# LiPo_Battery_Charger_MCP73831.net
KiCad netlist of a schematic drawn in EAGLE
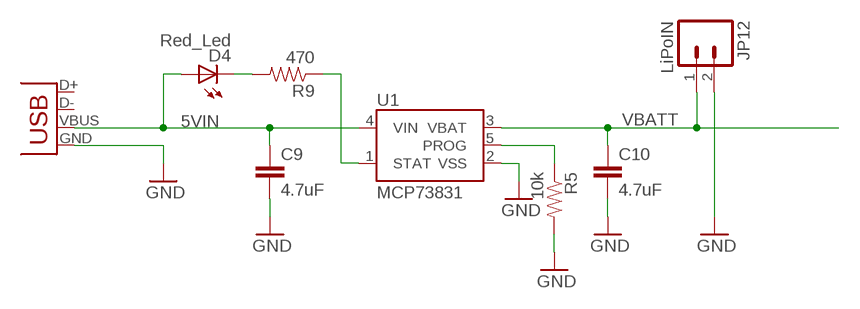
[diagram p0: schematic, sheet 1]

(export (version "E")
  (design (tool "Eeschema 10.0.6"))
  (components
    (comp (ref "C9")
      (value "4.7uF")
      (footprint "eagle-import:0402-CAP")
      (libsource (lib "eagle-import") (part "CAP0402-CAP"))
    )
    (comp (ref "C10")
      (value "4.7uF")
      (footprint "eagle-import:0402-CAP")
      (libsource (lib "eagle-import") (part "CAP0402-CAP"))
    )
    (comp (ref "D4")
      (value "Red_Led")
      (footprint "eagle-import:LED-0603")
      (libsource (lib "eagle-import") (part "LED0603"))
    )
    (comp (ref "JP12")
      (value "LiPoIN")
      (footprint "eagle-import:1X02")
      (libsource (lib "eagle-import") (part "M02PTH"))
    )
    (comp (ref "R5")
      (value "10k")
      (footprint "eagle-import:0402-RES")
      (libsource (lib "eagle-import") (part "RESISTOR0402-RES"))
    )
    (comp (ref "R9")
      (value "470")
      (footprint "eagle-import:0402-RES")
      (libsource (lib "eagle-import") (part "RESISTOR0402-RES"))
    )
    (comp (ref "U1")
      (value "MCP73831")
      (footprint "eagle-import:SOT23-5")
      (libsource (lib "eagle-import") (part "MCP73831"))
    )
    (comp (ref "X1")
      (value "USB-MICROB")
      (footprint "eagle-import:USB-MICROB")
      (libsource (lib "eagle-import") (part "USB-MICROB"))
    )
  )
  (nets
    (net (code "1") (name "/5VIN") (class "Default")
      (node (ref "C9") (pin "1") (pinfunction "1_1") (pintype "passive"))
      (node (ref "D4") (pin "A") (pinfunction "A_A") (pintype "passive"))
      (node (ref "U1") (pin "4") (pinfunction "VIN_4") (pintype "power_in"))
      (node (ref "X1") (pin "VBUS") (pinfunction "VBUS_VBUS") (pintype "bidirectional"))
    )
    (net (code "2") (name "/VBATT") (class "Default")
      (node (ref "C10") (pin "1") (pinfunction "1_1") (pintype "passive"))
      (node (ref "JP12") (pin "1") (pinfunction "1_1") (pintype "passive"))
      (node (ref "U1") (pin "3") (pinfunction "VBAT_3") (pintype "power_in"))
    )
    (net (code "3") (name "GND") (class "Default")
      (node (ref "C10") (pin "2") (pinfunction "2_2") (pintype "passive"))
      (node (ref "C9") (pin "2") (pinfunction "2_2") (pintype "passive"))
      (node (ref "JP12") (pin "2") (pinfunction "2_2") (pintype "passive"))
      (node (ref "R5") (pin "2") (pinfunction "2_2") (pintype "passive"))
      (node (ref "U1") (pin "2") (pinfunction "VSS_2") (pintype "power_in"))
      (node (ref "X1") (pin "GND") (pinfunction "GND_GND") (pintype "bidirectional"))
    )
    (net (code "4") (name "Net-(D4-PadC)") (class "Default")
      (node (ref "D4") (pin "C") (pinfunction "C_C") (pintype "passive"))
      (node (ref "R9") (pin "2") (pinfunction "2_2") (pintype "passive"))
    )
    (net (code "5") (name "Net-(U1-PROG)") (class "Default")
      (node (ref "R5") (pin "1") (pinfunction "1_1") (pintype "passive"))
      (node (ref "U1") (pin "5") (pinfunction "PROG_5") (pintype "input"))
    )
    (net (code "6") (name "Net-(U1-STAT)") (class "Default")
      (node (ref "R9") (pin "1") (pinfunction "1_1") (pintype "passive"))
      (node (ref "U1") (pin "1") (pinfunction "STAT_1") (pintype "output"))
    )
    (net (code "7") (name "unconnected-(X1-PadD+)") (class "Default")
      (node (ref "X1") (pin "D+") (pinfunction "D+_D+") (pintype "bidirectional"))
    )
    (net (code "8") (name "unconnected-(X1-PadD-)") (class "Default")
      (node (ref "X1") (pin "D-") (pinfunction "D-_D-") (pintype "bidirectional"))
    )
  )
)
